# G007C.net
KiCad netlist of a schematic drawn in EAGLE
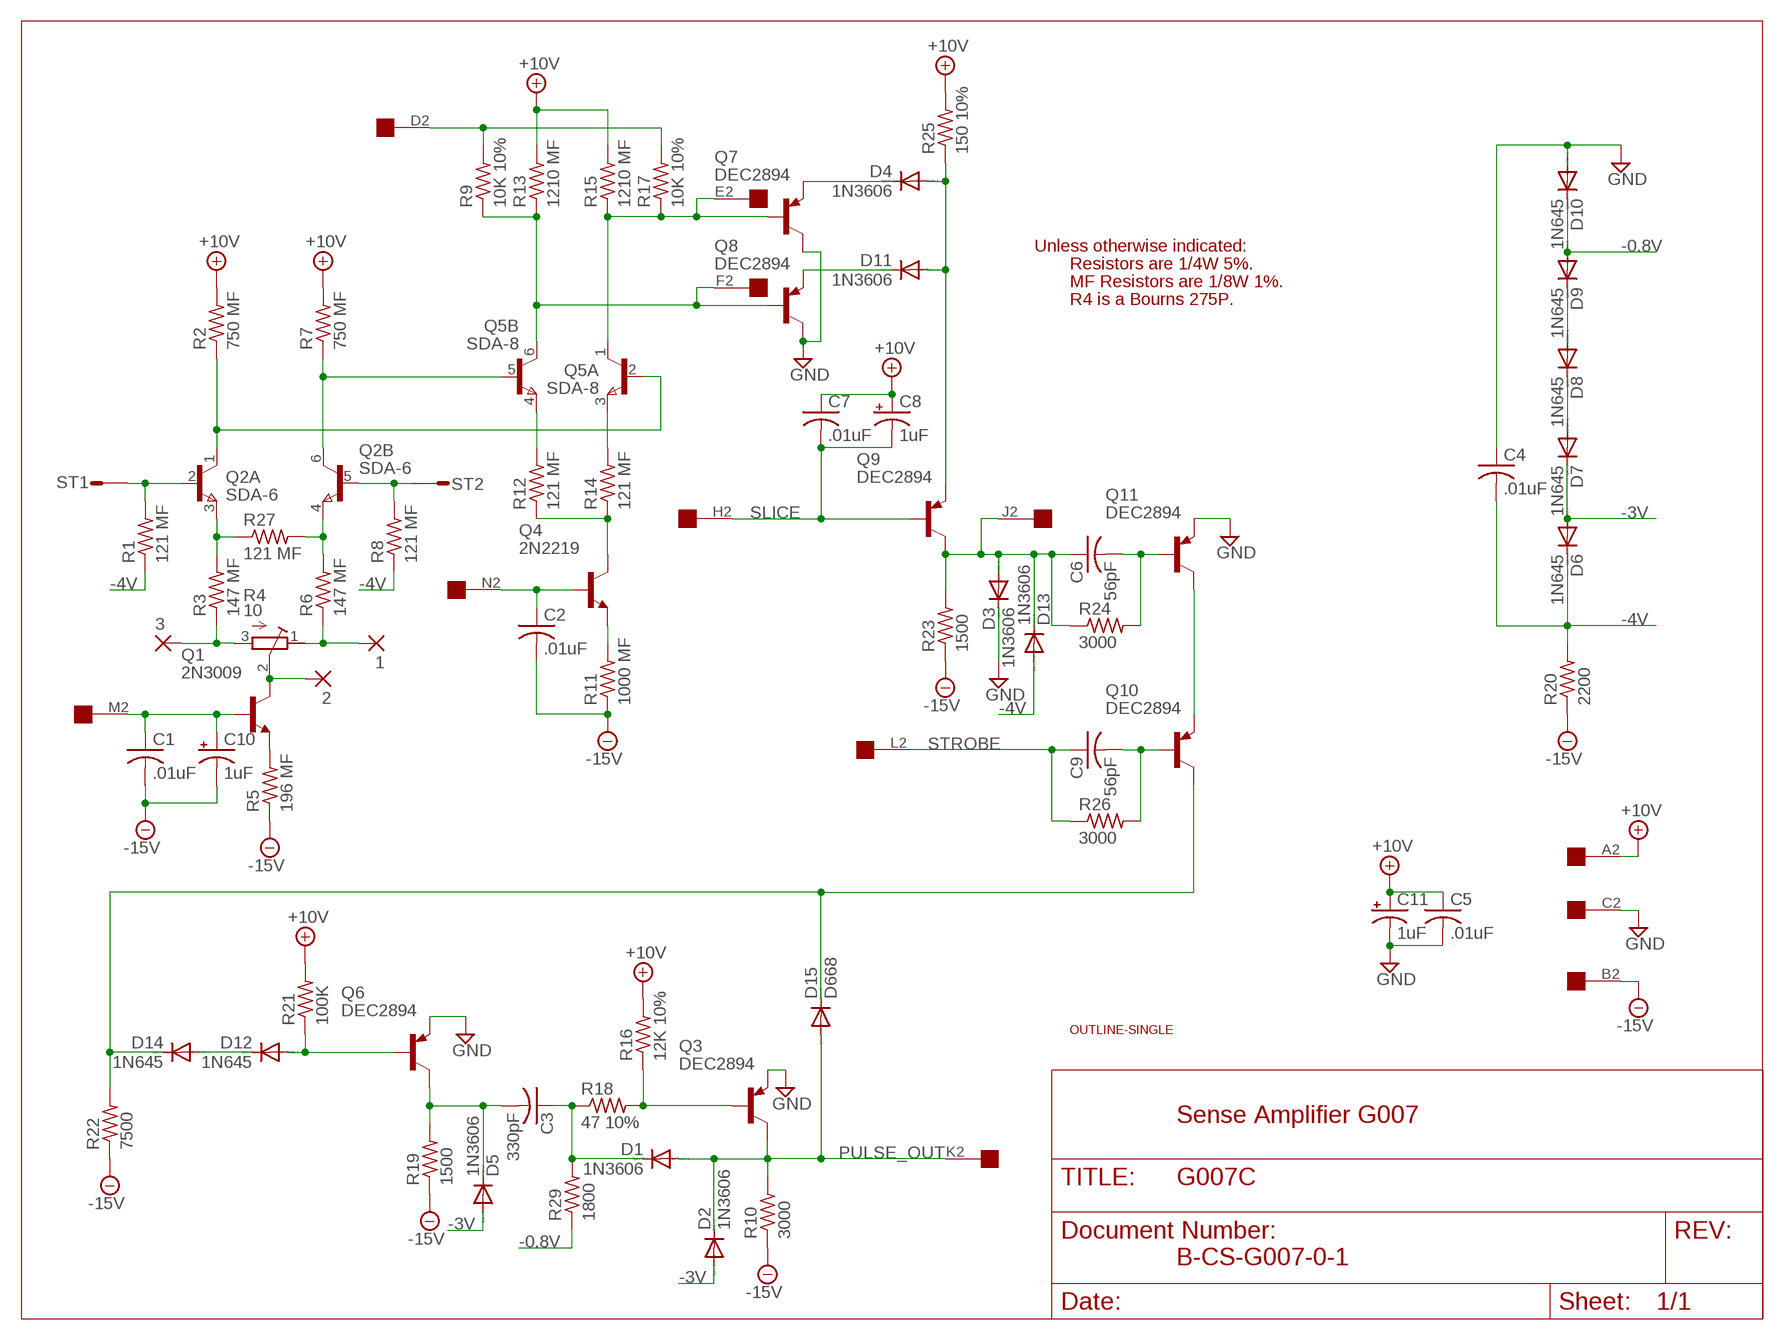
[diagram p0: schematic, sheet 1]

(export (version "E")
  (design (tool "Eeschema 10.0.6"))
  (components
    (comp (ref "1")
      (value "2,54/0,8")
      (footprint "eagle-import:2,54_0,8")
      (libsource (lib "eagle-import") (part "2,54/0,8"))
    )
    (comp (ref "2")
      (value "2,54/0,8")
      (footprint "eagle-import:2,54_0,8")
      (libsource (lib "eagle-import") (part "2,54/0,8"))
    )
    (comp (ref "3")
      (value "2,54/0,8")
      (footprint "eagle-import:2,54_0,8")
      (libsource (lib "eagle-import") (part "2,54/0,8"))
    )
    (comp (ref "C1")
      (value ".01uF")
      (footprint "eagle-import:C050-025X075")
      (libsource (lib "eagle-import") (part "C-US050-025X075"))
    )
    (comp (ref "C2")
      (value ".01uF")
      (footprint "eagle-import:C050-025X075")
      (libsource (lib "eagle-import") (part "C-US050-025X075"))
    )
    (comp (ref "C3")
      (value "330pF")
      (footprint "eagle-import:C075-032X103")
      (libsource (lib "eagle-import") (part "C-US075-032X103"))
    )
    (comp (ref "C4")
      (value ".01uF")
      (footprint "eagle-import:C050-025X075")
      (libsource (lib "eagle-import") (part "C-US050-025X075"))
    )
    (comp (ref "C5")
      (value ".01uF")
      (footprint "eagle-import:C050-025X075")
      (libsource (lib "eagle-import") (part "C-US050-025X075"))
    )
    (comp (ref "C6")
      (value "56pF")
      (footprint "eagle-import:C075-032X103")
      (libsource (lib "eagle-import") (part "C-US075-032X103"))
    )
    (comp (ref "C7")
      (value ".01uF")
      (footprint "eagle-import:C050-025X075")
      (libsource (lib "eagle-import") (part "C-US050-025X075"))
    )
    (comp (ref "C8")
      (value "1uF")
      (footprint "eagle-import:E12-4")
      (libsource (lib "eagle-import") (part "CPOL-USE12-4AXIAL"))
    )
    (comp (ref "C9")
      (value "56pF")
      (footprint "eagle-import:C075-032X103")
      (libsource (lib "eagle-import") (part "C-US075-032X103"))
    )
    (comp (ref "C10")
      (value "1uF")
      (footprint "eagle-import:E12-4")
      (libsource (lib "eagle-import") (part "CPOL-USE12-4AXIAL"))
    )
    (comp (ref "C11")
      (value "1uF")
      (footprint "eagle-import:E12-4")
      (libsource (lib "eagle-import") (part "CPOL-USE12-4AXIAL"))
    )
    (comp (ref "D1")
      (value "1N3606")
      (footprint "eagle-import:DO35-10")
      (libsource (lib "eagle-import") (part "1N4148DO35-10"))
    )
    (comp (ref "D2")
      (value "1N3606")
      (footprint "eagle-import:DO35-10")
      (libsource (lib "eagle-import") (part "1N4148DO35-10"))
    )
    (comp (ref "D3")
      (value "1N3606")
      (footprint "eagle-import:DO35-10")
      (libsource (lib "eagle-import") (part "1N4148DO35-10"))
    )
    (comp (ref "D4")
      (value "1N3606")
      (footprint "eagle-import:DO35-10")
      (libsource (lib "eagle-import") (part "1N4148DO35-10"))
    )
    (comp (ref "D5")
      (value "1N3606")
      (footprint "eagle-import:DO35-10")
      (libsource (lib "eagle-import") (part "1N4148DO35-10"))
    )
    (comp (ref "D6")
      (value "1N645")
      (footprint "eagle-import:DO35-10")
      (libsource (lib "eagle-import") (part "1N4148DO35-10"))
    )
    (comp (ref "D7")
      (value "1N645")
      (footprint "eagle-import:DO35-10")
      (libsource (lib "eagle-import") (part "1N4148DO35-10"))
    )
    (comp (ref "D8")
      (value "1N645")
      (footprint "eagle-import:DO35-10")
      (libsource (lib "eagle-import") (part "1N4148DO35-10"))
    )
    (comp (ref "D9")
      (value "1N645")
      (footprint "eagle-import:DO35-10")
      (libsource (lib "eagle-import") (part "1N4148DO35-10"))
    )
    (comp (ref "D10")
      (value "1N645")
      (footprint "eagle-import:DO35-10")
      (libsource (lib "eagle-import") (part "1N4148DO35-10"))
    )
    (comp (ref "D11")
      (value "1N3606")
      (footprint "eagle-import:DO35-10")
      (libsource (lib "eagle-import") (part "1N4148DO35-10"))
    )
    (comp (ref "D12")
      (value "1N645")
      (footprint "eagle-import:DO35-10")
      (libsource (lib "eagle-import") (part "1N4148DO35-10"))
    )
    (comp (ref "D13")
      (value "1N3606")
      (footprint "eagle-import:DO35-10")
      (libsource (lib "eagle-import") (part "1N4148DO35-10"))
    )
    (comp (ref "D14")
      (value "1N645")
      (footprint "eagle-import:DO35-10")
      (libsource (lib "eagle-import") (part "1N4148DO35-10"))
    )
    (comp (ref "D15")
      (value "D668")
      (footprint "eagle-import:DO35-10")
      (libsource (lib "eagle-import") (part "1N4148DO35-10"))
    )
    (comp (ref "Q1")
      (value "2N3009")
      (footprint "eagle-import:TO5")
      (libsource (lib "eagle-import") (part "2N2102"))
    )
    (comp (ref "Q2")
      (value "SDA-6")
      (footprint "eagle-import:TO78")
      (libsource (lib "eagle-import") (part "MAT-02H"))
    )
    (comp (ref "Q3")
      (value "DEC2894")
      (footprint "eagle-import:TO39")
      (libsource (lib "eagle-import") (part "2N2904"))
    )
    (comp (ref "Q4")
      (value "2N2219")
      (footprint "eagle-import:TO5")
      (libsource (lib "eagle-import") (part "2N2102"))
    )
    (comp (ref "Q5")
      (value "SDA-8")
      (footprint "eagle-import:TO78")
      (libsource (lib "eagle-import") (part "MAT-02H"))
    )
    (comp (ref "Q6")
      (value "DEC2894")
      (footprint "eagle-import:TO39")
      (libsource (lib "eagle-import") (part "2N2904"))
    )
    (comp (ref "Q7")
      (value "DEC2894")
      (footprint "eagle-import:TO39")
      (libsource (lib "eagle-import") (part "2N2904"))
    )
    (comp (ref "Q8")
      (value "DEC2894")
      (footprint "eagle-import:TO39")
      (libsource (lib "eagle-import") (part "2N2904"))
    )
    (comp (ref "Q9")
      (value "DEC2894")
      (footprint "eagle-import:TO39")
      (libsource (lib "eagle-import") (part "2N2904"))
    )
    (comp (ref "Q10")
      (value "DEC2894")
      (footprint "eagle-import:TO39")
      (libsource (lib "eagle-import") (part "2N2904"))
    )
    (comp (ref "Q11")
      (value "DEC2894")
      (footprint "eagle-import:TO39")
      (libsource (lib "eagle-import") (part "2N2904"))
    )
    (comp (ref "R1")
      (value "121 MF")
      (footprint "eagle-import:0207_12")
      (libsource (lib "eagle-import") (part "R-US_0207/12"))
    )
    (comp (ref "R2")
      (value "750 MF")
      (footprint "eagle-import:0207_12")
      (libsource (lib "eagle-import") (part "R-US_0207/12"))
    )
    (comp (ref "R3")
      (value "147 MF")
      (footprint "eagle-import:0207_12")
      (libsource (lib "eagle-import") (part "R-US_0207/12"))
    )
    (comp (ref "R4")
      (value "10")
      (footprint "eagle-import:3006Y")
      (libsource (lib "eagle-import") (part "275P"))
    )
    (comp (ref "R5")
      (value "196 MF")
      (footprint "eagle-import:0207_12")
      (libsource (lib "eagle-import") (part "R-US_0207/12"))
    )
    (comp (ref "R6")
      (value "147 MF")
      (footprint "eagle-import:0207_12")
      (libsource (lib "eagle-import") (part "R-US_0207/12"))
    )
    (comp (ref "R7")
      (value "750 MF")
      (footprint "eagle-import:0207_12")
      (libsource (lib "eagle-import") (part "R-US_0207/12"))
    )
    (comp (ref "R8")
      (value "121 MF")
      (footprint "eagle-import:0207_12")
      (libsource (lib "eagle-import") (part "R-US_0207/12"))
    )
    (comp (ref "R9")
      (value "10K 10%")
      (footprint "eagle-import:0207_10")
      (libsource (lib "eagle-import") (part "R-US_0207/10"))
    )
    (comp (ref "R10")
      (value "3000")
      (footprint "eagle-import:0207_10")
      (libsource (lib "eagle-import") (part "R-US_0207/10"))
    )
    (comp (ref "R11")
      (value "1000 MF")
      (footprint "eagle-import:0207_12")
      (libsource (lib "eagle-import") (part "R-US_0207/12"))
    )
    (comp (ref "R12")
      (value "121 MF")
      (footprint "eagle-import:0207_12")
      (libsource (lib "eagle-import") (part "R-US_0207/12"))
    )
    (comp (ref "R13")
      (value "1210 MF")
      (footprint "eagle-import:0207_12")
      (libsource (lib "eagle-import") (part "R-US_0207/12"))
    )
    (comp (ref "R14")
      (value "121 MF")
      (footprint "eagle-import:0207_12")
      (libsource (lib "eagle-import") (part "R-US_0207/12"))
    )
    (comp (ref "R15")
      (value "1210 MF")
      (footprint "eagle-import:0207_12")
      (libsource (lib "eagle-import") (part "R-US_0207/12"))
    )
    (comp (ref "R16")
      (value "12K 10%")
      (footprint "eagle-import:0207_10")
      (libsource (lib "eagle-import") (part "R-US_0207/10"))
    )
    (comp (ref "R17")
      (value "10K 10%")
      (footprint "eagle-import:0207_10")
      (libsource (lib "eagle-import") (part "R-US_0207/10"))
    )
    (comp (ref "R18")
      (value "47 10%")
      (footprint "eagle-import:0207_10")
      (libsource (lib "eagle-import") (part "R-US_0207/10"))
    )
    (comp (ref "R19")
      (value "1500")
      (footprint "eagle-import:0207_10")
      (libsource (lib "eagle-import") (part "R-US_0207/10"))
    )
    (comp (ref "R20")
      (value "2200")
      (footprint "eagle-import:0207_10")
      (libsource (lib "eagle-import") (part "R-US_0207/10"))
    )
    (comp (ref "R21")
      (value "100K")
      (footprint "eagle-import:0207_10")
      (libsource (lib "eagle-import") (part "R-US_0207/10"))
    )
    (comp (ref "R22")
      (value "7500")
      (footprint "eagle-import:0207_10")
      (libsource (lib "eagle-import") (part "R-US_0207/10"))
    )
    (comp (ref "R23")
      (value "1500")
      (footprint "eagle-import:0207_10")
      (libsource (lib "eagle-import") (part "R-US_0207/10"))
    )
    (comp (ref "R24")
      (value "3000")
      (footprint "eagle-import:0207_10")
      (libsource (lib "eagle-import") (part "R-US_0207/10"))
    )
    (comp (ref "R25")
      (value "150 10%")
      (footprint "eagle-import:0207_10")
      (libsource (lib "eagle-import") (part "R-US_0207/10"))
    )
    (comp (ref "R26")
      (value "3000")
      (footprint "eagle-import:0207_10")
      (libsource (lib "eagle-import") (part "R-US_0207/10"))
    )
    (comp (ref "R27")
      (value "121 MF")
      (footprint "eagle-import:0207_12")
      (libsource (lib "eagle-import") (part "R-US_0207/12"))
    )
    (comp (ref "R29")
      (value "1800")
      (footprint "eagle-import:0207_10")
      (libsource (lib "eagle-import") (part "R-US_0207/10"))
    )
    (comp (ref "ST1")
      (value "ST2,8")
      (footprint "eagle-import:ST2,8")
      (libsource (lib "eagle-import") (part "ST2,8"))
    )
    (comp (ref "ST2")
      (value "ST2,8")
      (footprint "eagle-import:ST2,8")
      (libsource (lib "eagle-import") (part "ST2,8"))
    )
    (comp (ref "U$1")
      (value "OUTLINE-SINGLE")
      (footprint "eagle-import:SINGLE")
      (libsource (lib "eagle-import") (part "OUTLINE-SINGLE"))
    )
    (comp (ref "U$2")
      (value "EDGE-1")
      (footprint "eagle-import:EDGE-CON1")
      (libsource (lib "eagle-import") (part "EDGE-1"))
    )
  )
  (nets
    (net (code "1") (name "+10V") (class "Default")
      (node (ref "C11") (pin "+") (pinfunction "+_+") (pintype "passive"))
      (node (ref "C5") (pin "1") (pinfunction "1_1") (pintype "passive"))
      (node (ref "C7") (pin "1") (pinfunction "1_1") (pintype "passive"))
      (node (ref "C8") (pin "+") (pinfunction "+_+") (pintype "passive"))
      (node (ref "R13") (pin "2") (pinfunction "2_2") (pintype "passive"))
      (node (ref "R15") (pin "2") (pinfunction "2_2") (pintype "passive"))
      (node (ref "R16") (pin "2") (pinfunction "2_2") (pintype "passive"))
      (node (ref "R2") (pin "2") (pinfunction "2_2") (pintype "passive"))
      (node (ref "R21") (pin "2") (pinfunction "2_2") (pintype "passive"))
      (node (ref "R25") (pin "2") (pinfunction "2_2") (pintype "passive"))
      (node (ref "R7") (pin "2") (pinfunction "2_2") (pintype "passive"))
      (node (ref "U$2") (pin "A2") (pinfunction "1_A2") (pintype "bidirectional"))
    )
    (net (code "2") (name "-15V") (class "Default")
      (node (ref "C1") (pin "2") (pinfunction "2_2") (pintype "passive"))
      (node (ref "C10") (pin "-") (pinfunction "-_-") (pintype "passive"))
      (node (ref "C2") (pin "2") (pinfunction "2_2") (pintype "passive"))
      (node (ref "R10") (pin "1") (pinfunction "1_1") (pintype "passive"))
      (node (ref "R11") (pin "1") (pinfunction "1_1") (pintype "passive"))
      (node (ref "R19") (pin "1") (pinfunction "1_1") (pintype "passive"))
      (node (ref "R20") (pin "1") (pinfunction "1_1") (pintype "passive"))
      (node (ref "R22") (pin "1") (pinfunction "1_1") (pintype "passive"))
      (node (ref "R23") (pin "1") (pinfunction "1_1") (pintype "passive"))
      (node (ref "R5") (pin "1") (pinfunction "1_1") (pintype "passive"))
      (node (ref "U$2") (pin "B2") (pinfunction "1_B2") (pintype "bidirectional"))
    )
    (net (code "3") (name "/-0.8V") (class "Default")
      (node (ref "D10") (pin "C") (pinfunction "C_C") (pintype "passive"))
      (node (ref "D9") (pin "A") (pinfunction "A_A") (pintype "passive"))
      (node (ref "R29") (pin "1") (pinfunction "1_1") (pintype "passive"))
    )
    (net (code "4") (name "/-3V") (class "Default")
      (node (ref "D2") (pin "A") (pinfunction "A_A") (pintype "passive"))
      (node (ref "D5") (pin "A") (pinfunction "A_A") (pintype "passive"))
      (node (ref "D6") (pin "A") (pinfunction "A_A") (pintype "passive"))
      (node (ref "D7") (pin "C") (pinfunction "C_C") (pintype "passive"))
    )
    (net (code "5") (name "/-4V") (class "Default")
      (node (ref "C4") (pin "2") (pinfunction "2_2") (pintype "passive"))
      (node (ref "D13") (pin "A") (pinfunction "A_A") (pintype "passive"))
      (node (ref "D6") (pin "C") (pinfunction "C_C") (pintype "passive"))
      (node (ref "R1") (pin "1") (pinfunction "1_1") (pintype "passive"))
      (node (ref "R20") (pin "2") (pinfunction "2_2") (pintype "passive"))
      (node (ref "R8") (pin "1") (pinfunction "1_1") (pintype "passive"))
    )
    (net (code "6") (name "/PULSE_OUT") (class "Default")
      (node (ref "D1") (pin "A") (pinfunction "A_A") (pintype "passive"))
      (node (ref "D15") (pin "A") (pinfunction "A_A") (pintype "passive"))
      (node (ref "D2") (pin "C") (pinfunction "C_C") (pintype "passive"))
      (node (ref "Q3") (pin "3") (pinfunction "C_3") (pintype "passive"))
      (node (ref "R10") (pin "2") (pinfunction "2_2") (pintype "passive"))
      (node (ref "U$2") (pin "K2") (pinfunction "1_K2") (pintype "bidirectional"))
    )
    (net (code "7") (name "/SLICE") (class "Default")
      (node (ref "C7") (pin "2") (pinfunction "2_2") (pintype "passive"))
      (node (ref "C8") (pin "-") (pinfunction "-_-") (pintype "passive"))
      (node (ref "Q9") (pin "2") (pinfunction "B_2") (pintype "passive"))
      (node (ref "U$2") (pin "H2") (pinfunction "1_H2") (pintype "bidirectional"))
    )
    (net (code "8") (name "/STROBE") (class "Default")
      (node (ref "C9") (pin "1") (pinfunction "1_1") (pintype "passive"))
      (node (ref "R26") (pin "1") (pinfunction "1_1") (pintype "passive"))
      (node (ref "U$2") (pin "L2") (pinfunction "1_L2") (pintype "bidirectional"))
    )
    (net (code "9") (name "GND") (class "Default")
      (node (ref "C11") (pin "-") (pinfunction "-_-") (pintype "passive"))
      (node (ref "C4") (pin "1") (pinfunction "1_1") (pintype "passive"))
      (node (ref "C5") (pin "2") (pinfunction "2_2") (pintype "passive"))
      (node (ref "D10") (pin "A") (pinfunction "A_A") (pintype "passive"))
      (node (ref "D3") (pin "C") (pinfunction "C_C") (pintype "passive"))
      (node (ref "Q11") (pin "1") (pinfunction "E_1") (pintype "passive"))
      (node (ref "Q3") (pin "1") (pinfunction "E_1") (pintype "passive"))
      (node (ref "Q6") (pin "1") (pinfunction "E_1") (pintype "passive"))
      (node (ref "Q7") (pin "3") (pinfunction "C_3") (pintype "passive"))
      (node (ref "Q8") (pin "3") (pinfunction "C_3") (pintype "passive"))
      (node (ref "U$2") (pin "C2") (pinfunction "1_C2") (pintype "bidirectional"))
    )
    (net (code "10") (name "Net-(1-P)") (class "Default")
      (node (ref "1") (pin "1") (pinfunction "P_1") (pintype "passive"))
      (node (ref "R4") (pin "1") (pinfunction "A_1") (pintype "passive"))
      (node (ref "R6") (pin "1") (pinfunction "1_1") (pintype "passive"))
    )
    (net (code "11") (name "Net-(2-P)") (class "Default")
      (node (ref "2") (pin "1") (pinfunction "P_1") (pintype "passive"))
      (node (ref "Q1") (pin "3") (pinfunction "C_3") (pintype "passive"))
      (node (ref "R4") (pin "2") (pinfunction "S_2") (pintype "passive"))
    )
    (net (code "12") (name "Net-(3-P)") (class "Default")
      (node (ref "3") (pin "1") (pinfunction "P_1") (pintype "passive"))
      (node (ref "R3") (pin "1") (pinfunction "1_1") (pintype "passive"))
      (node (ref "R4") (pin "3") (pinfunction "E_3") (pintype "passive"))
    )
    (net (code "13") (name "Net-(C3-Pad1)") (class "Default")
      (node (ref "C3") (pin "1") (pinfunction "1_1") (pintype "passive"))
      (node (ref "D1") (pin "C") (pinfunction "C_C") (pintype "passive"))
      (node (ref "R18") (pin "1") (pinfunction "1_1") (pintype "passive"))
      (node (ref "R29") (pin "2") (pinfunction "2_2") (pintype "passive"))
    )
    (net (code "14") (name "Net-(D7-PadA)") (class "Default")
      (node (ref "D7") (pin "A") (pinfunction "A_A") (pintype "passive"))
      (node (ref "D8") (pin "C") (pinfunction "C_C") (pintype "passive"))
    )
    (net (code "15") (name "Net-(D8-PadA)") (class "Default")
      (node (ref "D8") (pin "A") (pinfunction "A_A") (pintype "passive"))
      (node (ref "D9") (pin "C") (pinfunction "C_C") (pintype "passive"))
    )
    (net (code "16") (name "Net-(D12-PadC)") (class "Default")
      (node (ref "D12") (pin "C") (pinfunction "C_C") (pintype "passive"))
      (node (ref "D14") (pin "A") (pinfunction "A_A") (pintype "passive"))
    )
    (net (code "17") (name "Net-(Q1-B)") (class "Default")
      (node (ref "C1") (pin "1") (pinfunction "1_1") (pintype "passive"))
      (node (ref "C10") (pin "+") (pinfunction "+_+") (pintype "passive"))
      (node (ref "Q1") (pin "2") (pinfunction "B_2") (pintype "passive"))
      (node (ref "U$2") (pin "M2") (pinfunction "1_M2") (pintype "bidirectional"))
    )
    (net (code "18") (name "Net-(Q1-E)") (class "Default")
      (node (ref "Q1") (pin "1") (pinfunction "E_1") (pintype "passive"))
      (node (ref "R5") (pin "2") (pinfunction "2_2") (pintype "passive"))
    )
    (net (code "19") (name "Net-(Q2A-B)") (class "Default")
      (node (ref "Q2") (pin "2") (pinfunction "B_2") (pintype "passive"))
      (node (ref "R1") (pin "2") (pinfunction "2_2") (pintype "passive"))
      (node (ref "ST1") (pin "1") (pinfunction "ST_1") (pintype "passive"))
    )
    (net (code "20") (name "Net-(Q2A-C)") (class "Default")
      (node (ref "Q2") (pin "1") (pinfunction "C_1") (pintype "passive"))
      (node (ref "Q5") (pin "2") (pinfunction "B_2") (pintype "passive"))
      (node (ref "R2") (pin "1") (pinfunction "1_1") (pintype "passive"))
    )
    (net (code "21") (name "Net-(Q2A-E)") (class "Default")
      (node (ref "Q2") (pin "3") (pinfunction "E_3") (pintype "passive"))
      (node (ref "R27") (pin "1") (pinfunction "1_1") (pintype "passive"))
      (node (ref "R3") (pin "2") (pinfunction "2_2") (pintype "passive"))
    )
    (net (code "22") (name "Net-(Q2B-B)") (class "Default")
      (node (ref "Q2") (pin "5") (pinfunction "B_5") (pintype "passive"))
      (node (ref "R8") (pin "2") (pinfunction "2_2") (pintype "passive"))
      (node (ref "ST2") (pin "1") (pinfunction "ST_1") (pintype "passive"))
    )
    (net (code "23") (name "Net-(Q2B-C)") (class "Default")
      (node (ref "Q2") (pin "6") (pinfunction "C_6") (pintype "passive"))
      (node (ref "Q5") (pin "5") (pinfunction "B_5") (pintype "passive"))
      (node (ref "R7") (pin "1") (pinfunction "1_1") (pintype "passive"))
    )
    (net (code "24") (name "Net-(Q2B-E)") (class "Default")
      (node (ref "Q2") (pin "4") (pinfunction "E_4") (pintype "passive"))
      (node (ref "R27") (pin "2") (pinfunction "2_2") (pintype "passive"))
      (node (ref "R6") (pin "2") (pinfunction "2_2") (pintype "passive"))
    )
    (net (code "25") (name "Net-(Q3-B)") (class "Default")
      (node (ref "Q3") (pin "2") (pinfunction "B_2") (pintype "passive"))
      (node (ref "R16") (pin "1") (pinfunction "1_1") (pintype "passive"))
      (node (ref "R18") (pin "2") (pinfunction "2_2") (pintype "passive"))
    )
    (net (code "26") (name "Net-(Q4-B)") (class "Default")
      (node (ref "C2") (pin "1") (pinfunction "1_1") (pintype "passive"))
      (node (ref "Q4") (pin "2") (pinfunction "B_2") (pintype "passive"))
      (node (ref "U$2") (pin "N2") (pinfunction "1_N2") (pintype "bidirectional"))
    )
    (net (code "27") (name "Net-(Q4-C)") (class "Default")
      (node (ref "Q4") (pin "3") (pinfunction "C_3") (pintype "passive"))
      (node (ref "R12") (pin "1") (pinfunction "1_1") (pintype "passive"))
      (node (ref "R14") (pin "1") (pinfunction "1_1") (pintype "passive"))
    )
    (net (code "28") (name "Net-(Q4-E)") (class "Default")
      (node (ref "Q4") (pin "1") (pinfunction "E_1") (pintype "passive"))
      (node (ref "R11") (pin "2") (pinfunction "2_2") (pintype "passive"))
    )
    (net (code "29") (name "Net-(Q5A-C)") (class "Default")
      (node (ref "Q5") (pin "1") (pinfunction "C_1") (pintype "passive"))
      (node (ref "Q7") (pin "2") (pinfunction "B_2") (pintype "passive"))
      (node (ref "R15") (pin "1") (pinfunction "1_1") (pintype "passive"))
      (node (ref "R17") (pin "1") (pinfunction "1_1") (pintype "passive"))
      (node (ref "U$2") (pin "E2") (pinfunction "1_E2") (pintype "bidirectional"))
    )
    (net (code "30") (name "Net-(Q5A-E)") (class "Default")
      (node (ref "Q5") (pin "3") (pinfunction "E_3") (pintype "passive"))
      (node (ref "R14") (pin "2") (pinfunction "2_2") (pintype "passive"))
    )
    (net (code "31") (name "Net-(Q5B-C)") (class "Default")
      (node (ref "Q5") (pin "6") (pinfunction "C_6") (pintype "passive"))
      (node (ref "Q8") (pin "2") (pinfunction "B_2") (pintype "passive"))
      (node (ref "R13") (pin "1") (pinfunction "1_1") (pintype "passive"))
      (node (ref "R9") (pin "1") (pinfunction "1_1") (pintype "passive"))
      (node (ref "U$2") (pin "F2") (pinfunction "1_F2") (pintype "bidirectional"))
    )
    (net (code "32") (name "Net-(Q5B-E)") (class "Default")
      (node (ref "Q5") (pin "4") (pinfunction "E_4") (pintype "passive"))
      (node (ref "R12") (pin "2") (pinfunction "2_2") (pintype "passive"))
    )
    (net (code "33") (name "Net-(Q6-B)") (class "Default")
      (node (ref "D12") (pin "A") (pinfunction "A_A") (pintype "passive"))
      (node (ref "Q6") (pin "2") (pinfunction "B_2") (pintype "passive"))
      (node (ref "R21") (pin "1") (pinfunction "1_1") (pintype "passive"))
    )
    (net (code "34") (name "Net-(Q6-C)") (class "Default")
      (node (ref "C3") (pin "2") (pinfunction "2_2") (pintype "passive"))
      (node (ref "D5") (pin "C") (pinfunction "C_C") (pintype "passive"))
      (node (ref "Q6") (pin "3") (pinfunction "C_3") (pintype "passive"))
      (node (ref "R19") (pin "2") (pinfunction "2_2") (pintype "passive"))
    )
    (net (code "35") (name "Net-(Q7-E)") (class "Default")
      (node (ref "D4") (pin "C") (pinfunction "C_C") (pintype "passive"))
      (node (ref "Q7") (pin "1") (pinfunction "E_1") (pintype "passive"))
    )
    (net (code "36") (name "Net-(Q8-E)") (class "Default")
      (node (ref "D11") (pin "C") (pinfunction "C_C") (pintype "passive"))
      (node (ref "Q8") (pin "1") (pinfunction "E_1") (pintype "passive"))
    )
    (net (code "37") (name "Net-(Q9-C)") (class "Default")
      (node (ref "C6") (pin "1") (pinfunction "1_1") (pintype "passive"))
      (node (ref "D13") (pin "C") (pinfunction "C_C") (pintype "passive"))
      (node (ref "D3") (pin "A") (pinfunction "A_A") (pintype "passive"))
      (node (ref "Q9") (pin "3") (pinfunction "C_3") (pintype "passive"))
      (node (ref "R23") (pin "2") (pinfunction "2_2") (pintype "passive"))
      (node (ref "R24") (pin "1") (pinfunction "1_1") (pintype "passive"))
      (node (ref "U$2") (pin "J2") (pinfunction "1_J2") (pintype "bidirectional"))
    )
    (net (code "38") (name "Net-(Q9-E)") (class "Default")
      (node (ref "D11") (pin "A") (pinfunction "A_A") (pintype "passive"))
      (node (ref "D4") (pin "A") (pinfunction "A_A") (pintype "passive"))
      (node (ref "Q9") (pin "1") (pinfunction "E_1") (pintype "passive"))
      (node (ref "R25") (pin "1") (pinfunction "1_1") (pintype "passive"))
    )
    (net (code "39") (name "Net-(Q10-B)") (class "Default")
      (node (ref "C9") (pin "2") (pinfunction "2_2") (pintype "passive"))
      (node (ref "Q10") (pin "2") (pinfunction "B_2") (pintype "passive"))
      (node (ref "R26") (pin "2") (pinfunction "2_2") (pintype "passive"))
    )
    (net (code "40") (name "Net-(Q10-C)") (class "Default")
      (node (ref "D14") (pin "C") (pinfunction "C_C") (pintype "passive"))
      (node (ref "D15") (pin "C") (pinfunction "C_C") (pintype "passive"))
      (node (ref "Q10") (pin "3") (pinfunction "C_3") (pintype "passive"))
      (node (ref "R22") (pin "2") (pinfunction "2_2") (pintype "passive"))
    )
    (net (code "41") (name "Net-(Q10-E)") (class "Default")
      (node (ref "Q10") (pin "1") (pinfunction "E_1") (pintype "passive"))
      (node (ref "Q11") (pin "3") (pinfunction "C_3") (pintype "passive"))
    )
    (net (code "42") (name "Net-(Q11-B)") (class "Default")
      (node (ref "C6") (pin "2") (pinfunction "2_2") (pintype "passive"))
      (node (ref "Q11") (pin "2") (pinfunction "B_2") (pintype "passive"))
      (node (ref "R24") (pin "2") (pinfunction "2_2") (pintype "passive"))
    )
    (net (code "43") (name "Net-(U$2D-1)") (class "Default")
      (node (ref "R17") (pin "2") (pinfunction "2_2") (pintype "passive"))
      (node (ref "R9") (pin "2") (pinfunction "2_2") (pintype "passive"))
      (node (ref "U$2") (pin "D2") (pinfunction "1_D2") (pintype "bidirectional"))
    )
  )
)
